# tx-qo100-v3.net
KiCad netlist of a schematic drawn in EAGLE
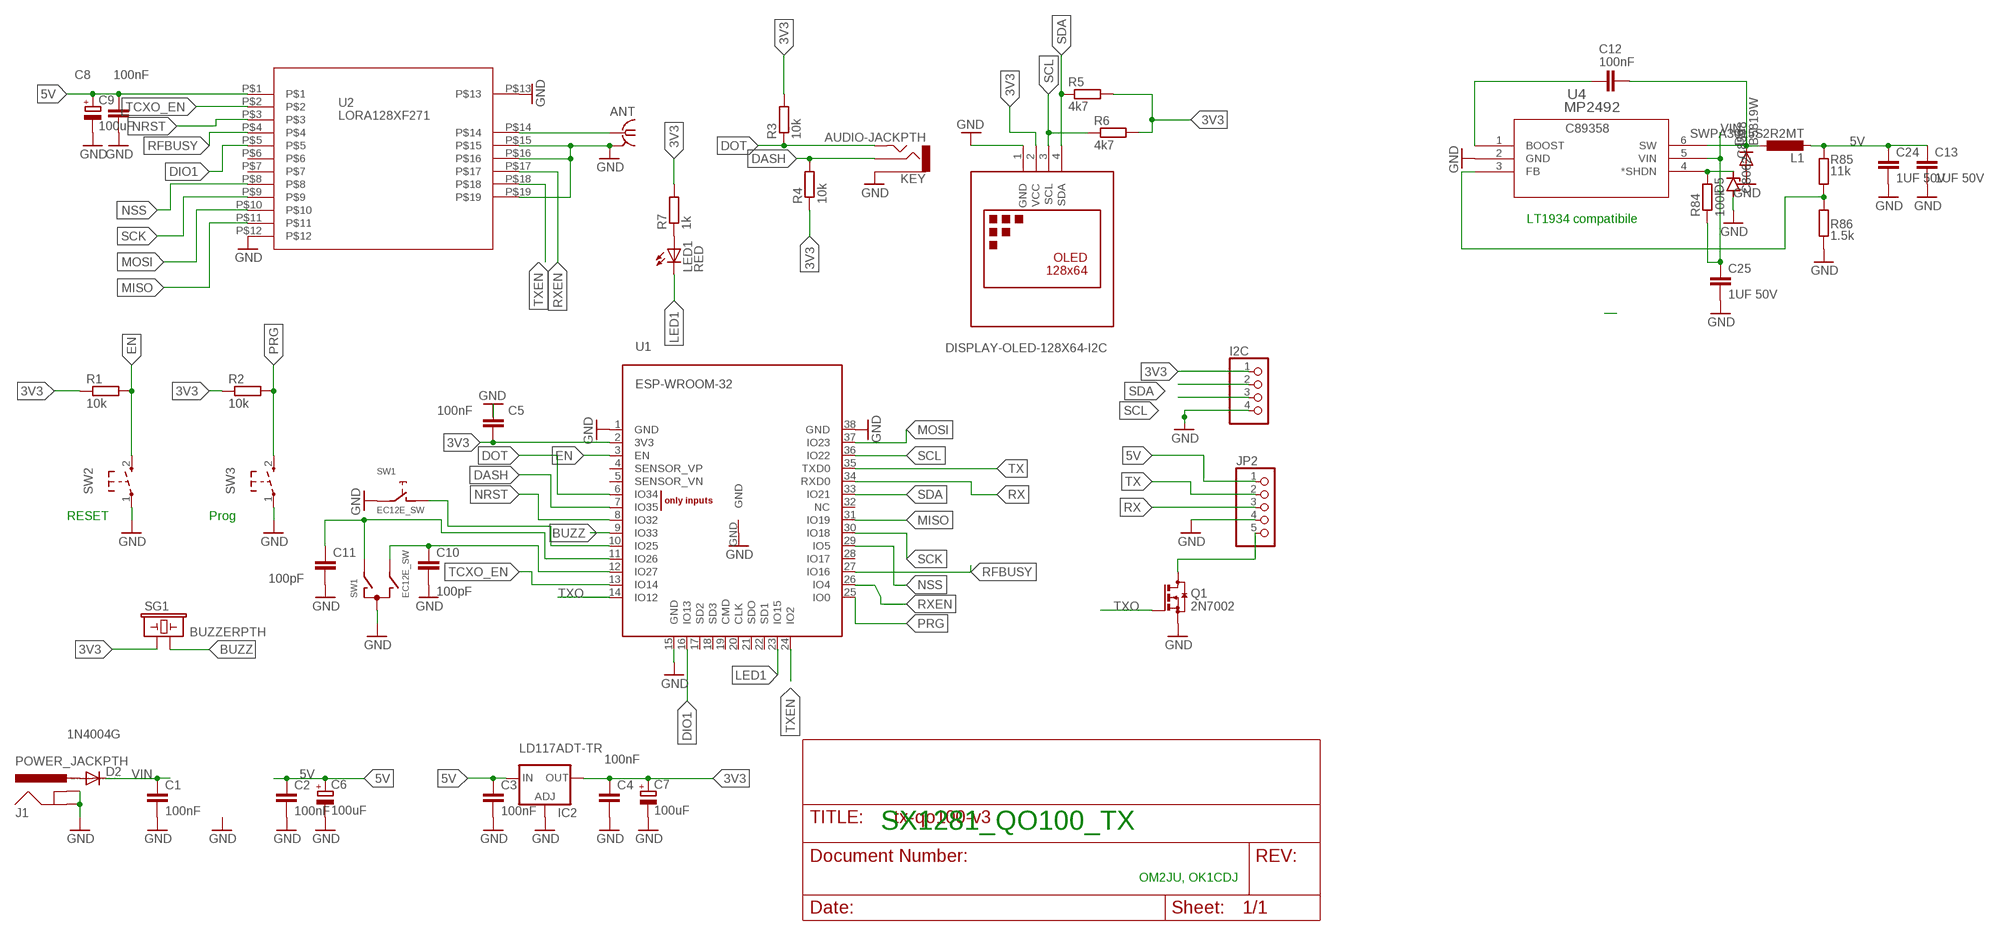
[diagram p0: schematic, sheet 1]

(export (version "E")
  (design (tool "Eeschema 10.0.6"))
  (components
    (comp (ref "ANT")
      (value "SMA-142-0711-821/826")
      (footprint "eagle-import:J502-ND-142-0711-821_826")
      (fields (field (name "MF") "JOHNSON COMPONENTS") (field (name "MPN") "142-0711-821"))
      (libsource (lib "eagle-import") (part "SMA-142-0711-821/826"))
    )
    (comp (ref "C1")
      (value "100nF")
      (footprint "eagle-import:C0603")
      (libsource (lib "eagle-import") (part "C-EUC0603"))
    )
    (comp (ref "C2")
      (value "100nF")
      (footprint "eagle-import:C0603")
      (libsource (lib "eagle-import") (part "C-EUC0603"))
    )
    (comp (ref "C3")
      (value "100nF")
      (footprint "eagle-import:C0603")
      (libsource (lib "eagle-import") (part "C-EUC0603"))
    )
    (comp (ref "C4")
      (value "100nF")
      (footprint "eagle-import:C0603")
      (libsource (lib "eagle-import") (part "C-EUC0603"))
    )
    (comp (ref "C5")
      (value "100nF")
      (footprint "eagle-import:C0603")
      (libsource (lib "eagle-import") (part "C-EUC0603"))
    )
    (comp (ref "C6")
      (value "100uF")
      (footprint "eagle-import:SMC_B")
      (fields (field (name "LCSC_PART") "C16133"))
      (libsource (lib "eagle-import") (part "CPOL-EUSMCB"))
    )
    (comp (ref "C7")
      (value "100uF")
      (footprint "eagle-import:SMC_B")
      (fields (field (name "LCSC_PART") "C16133"))
      (libsource (lib "eagle-import") (part "CPOL-EUSMCB"))
    )
    (comp (ref "C8")
      (value "100nF")
      (footprint "eagle-import:C0603")
      (libsource (lib "eagle-import") (part "C-EUC0603"))
    )
    (comp (ref "C9")
      (value "100uF")
      (footprint "eagle-import:SMC_B")
      (fields (field (name "LCSC_PART") "C16133"))
      (libsource (lib "eagle-import") (part "CPOL-EUSMCB"))
    )
    (comp (ref "C10")
      (value "100pF")
      (footprint "eagle-import:C0603")
      (libsource (lib "eagle-import") (part "C-EUC0603"))
    )
    (comp (ref "C11")
      (value "100pF")
      (footprint "eagle-import:C0603")
      (libsource (lib "eagle-import") (part "C-EUC0603"))
    )
    (comp (ref "C12")
      (value "100nF")
      (footprint "eagle-import:C0603")
      (libsource (lib "eagle-import") (part "C-EUC0603"))
    )
    (comp (ref "C13")
      (value "1UF 50V")
      (footprint "eagle-import:C0603")
      (fields (field (name "LCSC_PART") "C15849"))
      (libsource (lib "eagle-import") (part "C-EUC0603"))
    )
    (comp (ref "C24")
      (value "1UF 50V")
      (footprint "eagle-import:C0603")
      (fields (field (name "LCSC_PART") "C15849"))
      (libsource (lib "eagle-import") (part "C-EUC0603"))
    )
    (comp (ref "C25")
      (value "1UF 50V")
      (footprint "eagle-import:C0603")
      (fields (field (name "LCSC_PART") "C15849"))
      (libsource (lib "eagle-import") (part "C-EUC0603"))
    )
    (comp (ref "D2")
      (value "1N4004G")
      (footprint "eagle-import:DO-214AC")
      (fields (field (name "LCSC_PART") "C433394"))
      (libsource (lib "eagle-import") (part "DIODE-DO-214AC"))
    )
    (comp (ref "D5")
      (value "C8062")
      (footprint "eagle-import:SOD80C")
      (libsource (lib "eagle-import") (part "ZENER-DIODESOD80C"))
    )
    (comp (ref "D6")
      (value "B5819W")
      (footprint "eagle-import:SOD123")
      (fields (field (name "LCSC_PART") "C8598"))
      (libsource (lib "eagle-import") (part "DIODE-SOD123"))
    )
    (comp (ref "I2C")
      (value "PINHD-1X4")
      (footprint "eagle-import:1X04")
      (libsource (lib "eagle-import") (part "PINHD-1X4"))
    )
    (comp (ref "IC2")
      (value "LD117ADT-TR")
      (footprint "eagle-import:DPACK")
      (fields (field (name "LCSC_PART") "C358375"))
      (libsource (lib "eagle-import") (part "LD117A?DT-TR"))
    )
    (comp (ref "J1")
      (value "POWER_JACKPTH")
      (footprint "eagle-import:POWER_JACK_PTH")
      (libsource (lib "eagle-import") (part "POWER_JACKPTH"))
    )
    (comp (ref "JP2")
      (value "PINHD-1X5/90")
      (footprint "eagle-import:1X05_90")
      (libsource (lib "eagle-import") (part "PINHD-1X5/90"))
    )
    (comp (ref "KEY")
      (value "AUDIO-JACKPTH")
      (footprint "eagle-import:AUDIO-JACK")
      (libsource (lib "eagle-import") (part "AUDIO-JACKPTH"))
    )
    (comp (ref "L1")
      (value "SWPA3015S2R2MT")
      (footprint "eagle-import:L2825P")
      (fields (field (name "LCSC_PART") "C43389"))
      (libsource (lib "eagle-import") (part "L-EUL2825P"))
    )
    (comp (ref "LED1")
      (value "RED")
      (footprint "eagle-import:CHIP-LED0805")
      (fields (field (name "LCSC_PART") "C84256"))
      (libsource (lib "eagle-import") (part "LEDCHIP-LED0805"))
    )
    (comp (ref "Q1")
      (value "2N7002")
      (footprint "eagle-import:SOT23")
      (fields (field (name "LCSC_PART") "C8545"))
      (libsource (lib "eagle-import") (part "BSS123"))
    )
    (comp (ref "R1")
      (value "10k")
      (footprint "eagle-import:R0603")
      (libsource (lib "eagle-import") (part "R-EU_R0603"))
    )
    (comp (ref "R2")
      (value "10k")
      (footprint "eagle-import:R0603")
      (libsource (lib "eagle-import") (part "R-EU_R0603"))
    )
    (comp (ref "R3")
      (value "10k")
      (footprint "eagle-import:R0603")
      (libsource (lib "eagle-import") (part "R-EU_R0603"))
    )
    (comp (ref "R4")
      (value "10k")
      (footprint "eagle-import:R0603")
      (libsource (lib "eagle-import") (part "R-EU_R0603"))
    )
    (comp (ref "R5")
      (value "4k7")
      (footprint "eagle-import:R0603")
      (libsource (lib "eagle-import") (part "R-EU_R0603"))
    )
    (comp (ref "R6")
      (value "4k7")
      (footprint "eagle-import:R0603")
      (libsource (lib "eagle-import") (part "R-EU_R0603"))
    )
    (comp (ref "R7")
      (value "1k")
      (footprint "eagle-import:R0603")
      (libsource (lib "eagle-import") (part "R-EU_R0603"))
    )
    (comp (ref "R84")
      (value "100k")
      (footprint "eagle-import:R0603")
      (libsource (lib "eagle-import") (part "R-EU_R0603"))
    )
    (comp (ref "R85")
      (value "11k")
      (footprint "eagle-import:R0603")
      (libsource (lib "eagle-import") (part "R-EU_R0603"))
    )
    (comp (ref "R86")
      (value "1.5k")
      (footprint "eagle-import:R0603")
      (libsource (lib "eagle-import") (part "R-EU_R0603"))
    )
    (comp (ref "SG1")
      (value "BUZZERPTH")
      (footprint "eagle-import:BUZZER-12MM")
      (fields (field (name "LCSC_PART") "C360607"))
      (libsource (lib "eagle-import") (part "BUZZERPTH"))
    )
    (comp (ref "SW1")
      (value "EC12E_SW")
      (footprint "eagle-import:ALPS_EC12E_SW")
      (fields (field (name "MPN") "EC12E2424407"))
      (libsource (lib "eagle-import") (part "EC12E_SW"))
    )
    (comp (ref "SW2")
      (value "SW_TACT_2P-3X6")
      (footprint "eagle-import:SW_TACT_3X6")
      (fields (field (name "LCSC_PART") "C520860"))
      (libsource (lib "eagle-import") (part "SW_TACT_2P-3X6"))
    )
    (comp (ref "SW3")
      (value "SW_TACT_2P-3X6")
      (footprint "eagle-import:SW_TACT_3X6")
      (fields (field (name "LCSC_PART") "C520860"))
      (libsource (lib "eagle-import") (part "SW_TACT_2P-3X6"))
    )
    (comp (ref "U$1")
      (value "DISPLAY-OLED-128X64-I2C")
      (footprint "eagle-import:DISPLAY-OLED-128X64-I2C")
      (libsource (lib "eagle-import") (part "DISPLAY-OLED-128X64-I2C"))
    )
    (comp (ref "U1")
      (value "ESP-WROOM-32")
      (footprint "eagle-import:ESP-WROOM-32")
      (libsource (lib "eagle-import") (part "ESP-WROOM-32"))
    )
    (comp (ref "U2")
      (value "LORA128XF271")
      (footprint "eagle-import:LORA128XF27")
      (libsource (lib "eagle-import") (part "LORA128XF271"))
    )
    (comp (ref "U4")
      (value "MP2492")
      (footprint "eagle-import:SOT-6_S")
      (fields
        (field (name "DIGI-KEY_PART_NUMBER") "LT1934ES6#TRMPBFCT-ND")
        (field (name "MF") "Linear Technology/Analog")
        (field (name "MP") "LT1934ES6#TRMPBF")
        (field (name "LCSC_PART") "C89358")
      )
      (libsource (lib "eagle-import") (part "LT1934ES6TRMPBF"))
    )
  )
  (nets
    (net (code "1") (name "/TXO") (class "Default")
      (node (ref "Q1") (pin "1") (pinfunction "G_1") (pintype "passive"))
      (node (ref "U1") (pin "14") (pinfunction "IO12_14") (pintype "bidirectional"))
    )
    (net (code "2") (name "/VIN") (class "Default")
      (node (ref "C1") (pin "1") (pinfunction "1_1") (pintype "passive"))
      (node (ref "C25") (pin "1") (pinfunction "1_1") (pintype "passive"))
      (node (ref "D2") (pin "C") (pinfunction "C_C") (pintype "passive"))
      (node (ref "R84") (pin "1") (pinfunction "1_1") (pintype "passive"))
      (node (ref "U4") (pin "5") (pinfunction "VIN_5") (pintype "power_in"))
    )
    (net (code "3") (name "3V3") (class "Default")
      (node (ref "C4") (pin "1") (pinfunction "1_1") (pintype "passive"))
      (node (ref "C5") (pin "1") (pinfunction "1_1") (pintype "passive"))
      (node (ref "C7") (pin "+") (pinfunction "+_+") (pintype "passive"))
      (node (ref "I2C") (pin "1") (pinfunction "1_1") (pintype "passive"))
      (node (ref "IC2") (pin "4") (pinfunction "OUT_4") (pintype "passive"))
      (node (ref "R1") (pin "1") (pinfunction "1_1") (pintype "passive"))
      (node (ref "R2") (pin "1") (pinfunction "1_1") (pintype "passive"))
      (node (ref "R3") (pin "2") (pinfunction "2_2") (pintype "passive"))
      (node (ref "R4") (pin "1") (pinfunction "1_1") (pintype "passive"))
      (node (ref "R5") (pin "2") (pinfunction "2_2") (pintype "passive"))
      (node (ref "R6") (pin "2") (pinfunction "2_2") (pintype "passive"))
      (node (ref "R7") (pin "2") (pinfunction "2_2") (pintype "passive"))
      (node (ref "SG1") (pin "+") (pinfunction "1_+") (pintype "passive"))
      (node (ref "U$1") (pin "2") (pinfunction "VCC_2") (pintype "power_in"))
      (node (ref "U1") (pin "2") (pinfunction "3V3_2") (pintype "bidirectional"))
    )
    (net (code "4") (name "5V") (class "Default")
      (node (ref "C13") (pin "1") (pinfunction "1_1") (pintype "passive"))
      (node (ref "C2") (pin "1") (pinfunction "1_1") (pintype "passive"))
      (node (ref "C24") (pin "1") (pinfunction "1_1") (pintype "passive"))
      (node (ref "C3") (pin "1") (pinfunction "1_1") (pintype "passive"))
      (node (ref "C6") (pin "+") (pinfunction "+_+") (pintype "passive"))
      (node (ref "C8") (pin "1") (pinfunction "1_1") (pintype "passive"))
      (node (ref "C9") (pin "+") (pinfunction "+_+") (pintype "passive"))
      (node (ref "IC2") (pin "3") (pinfunction "IN_3") (pintype "input"))
      (node (ref "JP2") (pin "1") (pinfunction "1_1") (pintype "passive"))
      (node (ref "L1") (pin "2") (pinfunction "2_2") (pintype "passive"))
      (node (ref "R85") (pin "1") (pinfunction "1_1") (pintype "passive"))
      (node (ref "U2") (pin "P$1") (pinfunction "P$1_P$1") (pintype "bidirectional"))
    )
    (net (code "5") (name "BUZZ") (class "Default")
      (node (ref "SG1") (pin "-") (pinfunction "2_-") (pintype "passive"))
      (node (ref "U1") (pin "9") (pinfunction "IO33_9") (pintype "bidirectional"))
    )
    (net (code "6") (name "DASH") (class "Default")
      (node (ref "KEY") (pin "2") (pinfunction "2_2") (pintype "bidirectional"))
      (node (ref "R4") (pin "2") (pinfunction "2_2") (pintype "passive"))
      (node (ref "U1") (pin "7") (pinfunction "IO35_7") (pintype "input"))
    )
    (net (code "7") (name "DIO1") (class "Default")
      (node (ref "U1") (pin "16") (pinfunction "IO13_16") (pintype "bidirectional"))
      (node (ref "U2") (pin "P$5") (pinfunction "P$5_P$5") (pintype "bidirectional"))
    )
    (net (code "8") (name "DOT") (class "Default")
      (node (ref "KEY") (pin "5") (pinfunction "5_5") (pintype "bidirectional"))
      (node (ref "R3") (pin "1") (pinfunction "1_1") (pintype "passive"))
      (node (ref "U1") (pin "6") (pinfunction "IO34_6") (pintype "input"))
    )
    (net (code "9") (name "EN") (class "Default")
      (node (ref "R1") (pin "2") (pinfunction "2_2") (pintype "passive"))
      (node (ref "SW2") (pin "2") (pinfunction "3_2") (pintype "passive"))
      (node (ref "U1") (pin "3") (pinfunction "EN_3") (pintype "bidirectional"))
    )
    (net (code "10") (name "GND") (class "Default")
      (node (ref "ANT") (pin "G@1") (pinfunction "2_G@1") (pintype "passive"))
      (node (ref "ANT") (pin "G@2") (pinfunction "2_G@2") (pintype "passive"))
      (node (ref "ANT") (pin "G@3") (pinfunction "2_G@3") (pintype "passive"))
      (node (ref "ANT") (pin "G@4") (pinfunction "2_G@4") (pintype "passive"))
      (node (ref "C1") (pin "2") (pinfunction "2_2") (pintype "passive"))
      (node (ref "C10") (pin "2") (pinfunction "2_2") (pintype "passive"))
      (node (ref "C11") (pin "2") (pinfunction "2_2") (pintype "passive"))
      (node (ref "C13") (pin "2") (pinfunction "2_2") (pintype "passive"))
      (node (ref "C2") (pin "2") (pinfunction "2_2") (pintype "passive"))
      (node (ref "C24") (pin "2") (pinfunction "2_2") (pintype "passive"))
      (node (ref "C25") (pin "2") (pinfunction "2_2") (pintype "passive"))
      (node (ref "C3") (pin "2") (pinfunction "2_2") (pintype "passive"))
      (node (ref "C4") (pin "2") (pinfunction "2_2") (pintype "passive"))
      (node (ref "C5") (pin "2") (pinfunction "2_2") (pintype "passive"))
      (node (ref "C6") (pin "-") (pinfunction "-_-") (pintype "passive"))
      (node (ref "C7") (pin "-") (pinfunction "-_-") (pintype "passive"))
      (node (ref "C8") (pin "2") (pinfunction "2_2") (pintype "passive"))
      (node (ref "C9") (pin "-") (pinfunction "-_-") (pintype "passive"))
      (node (ref "D5") (pin "A") (pinfunction "A_A") (pintype "passive"))
      (node (ref "D6") (pin "A") (pinfunction "A_A") (pintype "passive"))
      (node (ref "I2C") (pin "4") (pinfunction "4_4") (pintype "passive"))
      (node (ref "IC2") (pin "1") (pinfunction "ADJ_1") (pintype "input"))
      (node (ref "J1") (pin "GND") (pinfunction "GND_GND") (pintype "bidirectional"))
      (node (ref "J1") (pin "GNDBREAK") (pinfunction "GNDBREAK_GNDBREAK") (pintype "bidirectional"))
      (node (ref "JP2") (pin "4") (pinfunction "4_4") (pintype "passive"))
      (node (ref "KEY") (pin "1") (pinfunction "1_1") (pintype "bidirectional"))
      (node (ref "Q1") (pin "2") (pinfunction "S_2") (pintype "passive"))
      (node (ref "R86") (pin "1") (pinfunction "1_1") (pintype "passive"))
      (node (ref "SW1") (pin "C") (pinfunction "C_C") (pintype "passive"))
      (node (ref "SW1") (pin "E") (pinfunction "2_E") (pintype "passive"))
      (node (ref "SW2") (pin "1") (pinfunction "1_1") (pintype "passive"))
      (node (ref "SW3") (pin "1") (pinfunction "1_1") (pintype "passive"))
      (node (ref "U$1") (pin "1") (pinfunction "GND_1") (pintype "power_in"))
      (node (ref "U1") (pin "1") (pinfunction "GND_1") (pintype "bidirectional"))
      (node (ref "U1") (pin "15") (pinfunction "GND_15") (pintype "bidirectional"))
      (node (ref "U1") (pin "38") (pinfunction "GND_38") (pintype "bidirectional"))
      (node (ref "U1") (pin "GND") (pinfunction "GND_GND") (pintype "bidirectional"))
      (node (ref "U2") (pin "P$12") (pinfunction "P$12_P$12") (pintype "bidirectional"))
      (node (ref "U2") (pin "P$13") (pinfunction "P$13_P$13") (pintype "bidirectional"))
      (node (ref "U2") (pin "P$15") (pinfunction "P$15_P$15") (pintype "bidirectional"))
      (node (ref "U2") (pin "P$16") (pinfunction "P$16_P$16") (pintype "bidirectional"))
      (node (ref "U2") (pin "P$19") (pinfunction "P$19_P$19") (pintype "bidirectional"))
      (node (ref "U4") (pin "2") (pinfunction "GND_2") (pintype "power_in"))
    )
    (net (code "11") (name "LED1") (class "Default")
      (node (ref "LED1") (pin "C") (pinfunction "C_C") (pintype "passive"))
      (node (ref "U1") (pin "23") (pinfunction "IO15_23") (pintype "bidirectional"))
    )
    (net (code "12") (name "MISO") (class "Default")
      (node (ref "U1") (pin "31") (pinfunction "IO19_31") (pintype "bidirectional"))
      (node (ref "U2") (pin "P$11") (pinfunction "P$11_P$11") (pintype "bidirectional"))
    )
    (net (code "13") (name "MOSI") (class "Default")
      (node (ref "U1") (pin "37") (pinfunction "IO23_37") (pintype "bidirectional"))
      (node (ref "U2") (pin "P$10") (pinfunction "P$10_P$10") (pintype "bidirectional"))
    )
    (net (code "14") (name "NRST") (class "Default")
      (node (ref "U1") (pin "8") (pinfunction "IO32_8") (pintype "bidirectional"))
      (node (ref "U2") (pin "P$3") (pinfunction "P$3_P$3") (pintype "bidirectional"))
    )
    (net (code "15") (name "NSS") (class "Default")
      (node (ref "U1") (pin "29") (pinfunction "IO5_29") (pintype "bidirectional"))
      (node (ref "U2") (pin "P$8") (pinfunction "P$8_P$8") (pintype "bidirectional"))
    )
    (net (code "16") (name "Net-(ANT-Pad1)") (class "Default")
      (node (ref "ANT") (pin "1") (pinfunction "1_1") (pintype "passive"))
      (node (ref "U2") (pin "P$14") (pinfunction "P$14_P$14") (pintype "bidirectional"))
    )
    (net (code "17") (name "Net-(D2-PadA)") (class "Default")
      (node (ref "D2") (pin "A") (pinfunction "A_A") (pintype "passive"))
      (node (ref "J1") (pin "PWR") (pinfunction "PWR_PWR") (pintype "bidirectional"))
    )
    (net (code "18") (name "Net-(LED1-PadA)") (class "Default")
      (node (ref "LED1") (pin "A") (pinfunction "A_A") (pintype "passive"))
      (node (ref "R7") (pin "1") (pinfunction "1_1") (pintype "passive"))
    )
    (net (code "19") (name "Net-(Q1-D)") (class "Default")
      (node (ref "JP2") (pin "5") (pinfunction "5_5") (pintype "passive"))
      (node (ref "Q1") (pin "3") (pinfunction "D_3") (pintype "passive"))
    )
    (net (code "20") (name "Net-(SW1B-1)") (class "Default")
      (node (ref "SW1") (pin "D") (pinfunction "1_D") (pintype "passive"))
      (node (ref "U1") (pin "10") (pinfunction "IO25_10") (pintype "bidirectional"))
    )
    (net (code "21") (name "Net-(U1-IO26)") (class "Default")
      (node (ref "C11") (pin "1") (pinfunction "1_1") (pintype "passive"))
      (node (ref "SW1") (pin "A") (pinfunction "A_A") (pintype "passive"))
      (node (ref "U1") (pin "11") (pinfunction "IO26_11") (pintype "bidirectional"))
    )
    (net (code "22") (name "Net-(U1-IO27)") (class "Default")
      (node (ref "C10") (pin "1") (pinfunction "1_1") (pintype "passive"))
      (node (ref "SW1") (pin "B") (pinfunction "B_B") (pintype "passive"))
      (node (ref "U1") (pin "12") (pinfunction "IO27_12") (pintype "bidirectional"))
    )
    (net (code "23") (name "Net-(U4-*SHDN)") (class "Default")
      (node (ref "D5") (pin "C") (pinfunction "C_C") (pintype "passive"))
      (node (ref "R84") (pin "2") (pinfunction "2_2") (pintype "passive"))
      (node (ref "U4") (pin "4") (pinfunction "*SHDN_4") (pintype "passive"))
    )
    (net (code "24") (name "Net-(U4-BOOST)") (class "Default")
      (node (ref "C12") (pin "2") (pinfunction "2_2") (pintype "passive"))
      (node (ref "U4") (pin "1") (pinfunction "BOOST_1") (pintype "passive"))
    )
    (net (code "25") (name "Net-(U4-FB)") (class "Default")
      (node (ref "R85") (pin "2") (pinfunction "2_2") (pintype "passive"))
      (node (ref "R86") (pin "2") (pinfunction "2_2") (pintype "passive"))
      (node (ref "U4") (pin "3") (pinfunction "FB_3") (pintype "passive"))
    )
    (net (code "26") (name "Net-(U4-SW)") (class "Default")
      (node (ref "C12") (pin "1") (pinfunction "1_1") (pintype "passive"))
      (node (ref "D6") (pin "C") (pinfunction "C_C") (pintype "passive"))
      (node (ref "L1") (pin "1") (pinfunction "1_1") (pintype "passive"))
      (node (ref "U4") (pin "6") (pinfunction "SW_6") (pintype "passive"))
    )
    (net (code "27") (name "PRG") (class "Default")
      (node (ref "R2") (pin "2") (pinfunction "2_2") (pintype "passive"))
      (node (ref "SW3") (pin "2") (pinfunction "3_2") (pintype "passive"))
      (node (ref "U1") (pin "25") (pinfunction "IO0_25") (pintype "bidirectional"))
    )
    (net (code "28") (name "RFBUSY") (class "Default")
      (node (ref "U1") (pin "27") (pinfunction "IO16_27") (pintype "bidirectional"))
      (node (ref "U2") (pin "P$4") (pinfunction "P$4_P$4") (pintype "bidirectional"))
    )
    (net (code "29") (name "RX") (class "Default")
      (node (ref "JP2") (pin "3") (pinfunction "3_3") (pintype "passive"))
      (node (ref "U1") (pin "34") (pinfunction "RXD0_34") (pintype "bidirectional"))
    )
    (net (code "30") (name "RXEN") (class "Default")
      (node (ref "U1") (pin "26") (pinfunction "IO4_26") (pintype "bidirectional"))
      (node (ref "U2") (pin "P$17") (pinfunction "P$17_P$17") (pintype "bidirectional"))
    )
    (net (code "31") (name "SCK") (class "Default")
      (node (ref "U1") (pin "30") (pinfunction "IO18_30") (pintype "bidirectional"))
      (node (ref "U2") (pin "P$9") (pinfunction "P$9_P$9") (pintype "bidirectional"))
    )
    (net (code "32") (name "SCL") (class "Default")
      (node (ref "I2C") (pin "3") (pinfunction "3_3") (pintype "passive"))
      (node (ref "R6") (pin "1") (pinfunction "1_1") (pintype "passive"))
      (node (ref "U$1") (pin "3") (pinfunction "SCL_3") (pintype "bidirectional"))
      (node (ref "U1") (pin "36") (pinfunction "IO22_36") (pintype "bidirectional"))
    )
    (net (code "33") (name "SDA") (class "Default")
      (node (ref "I2C") (pin "2") (pinfunction "2_2") (pintype "passive"))
      (node (ref "R5") (pin "1") (pinfunction "1_1") (pintype "passive"))
      (node (ref "U$1") (pin "4") (pinfunction "SDA_4") (pintype "bidirectional"))
      (node (ref "U1") (pin "33") (pinfunction "IO21_33") (pintype "bidirectional"))
    )
    (net (code "34") (name "TCXO_EN") (class "Default")
      (node (ref "U1") (pin "13") (pinfunction "IO14_13") (pintype "bidirectional"))
      (node (ref "U2") (pin "P$2") (pinfunction "P$2_P$2") (pintype "bidirectional"))
    )
    (net (code "35") (name "TX") (class "Default")
      (node (ref "JP2") (pin "2") (pinfunction "2_2") (pintype "passive"))
      (node (ref "U1") (pin "35") (pinfunction "TXD0_35") (pintype "bidirectional"))
    )
    (net (code "36") (name "TXEN") (class "Default")
      (node (ref "U1") (pin "24") (pinfunction "IO2_24") (pintype "bidirectional"))
      (node (ref "U2") (pin "P$18") (pinfunction "P$18_P$18") (pintype "bidirectional"))
    )
    (net (code "37") (name "unconnected-(U1-CLK-Pad20)") (class "Default")
      (node (ref "U1") (pin "20") (pinfunction "CLK_20") (pintype "bidirectional"))
    )
    (net (code "38") (name "unconnected-(U1-CMD-Pad19)") (class "Default")
      (node (ref "U1") (pin "19") (pinfunction "CMD_19") (pintype "bidirectional"))
    )
    (net (code "39") (name "unconnected-(U1-IO17-Pad28)") (class "Default")
      (node (ref "U1") (pin "28") (pinfunction "IO17_28") (pintype "bidirectional"))
    )
    (net (code "40") (name "unconnected-(U1-NC-Pad32)") (class "Default")
      (node (ref "U1") (pin "32") (pinfunction "NC_32") (pintype "bidirectional"))
    )
    (net (code "41") (name "unconnected-(U1-SD1-Pad22)") (class "Default")
      (node (ref "U1") (pin "22") (pinfunction "SD1_22") (pintype "bidirectional"))
    )
    (net (code "42") (name "unconnected-(U1-SD2-Pad17)") (class "Default")
      (node (ref "U1") (pin "17") (pinfunction "SD2_17") (pintype "bidirectional"))
    )
    (net (code "43") (name "unconnected-(U1-SD3-Pad18)") (class "Default")
      (node (ref "U1") (pin "18") (pinfunction "SD3_18") (pintype "bidirectional"))
    )
    (net (code "44") (name "unconnected-(U1-SDO-Pad21)") (class "Default")
      (node (ref "U1") (pin "21") (pinfunction "SDO_21") (pintype "bidirectional"))
    )
    (net (code "45") (name "unconnected-(U1-SENSOR_VN-Pad5)") (class "Default")
      (node (ref "U1") (pin "5") (pinfunction "SENSOR_VN_5") (pintype "input"))
    )
    (net (code "46") (name "unconnected-(U1-SENSOR_VP-Pad4)") (class "Default")
      (node (ref "U1") (pin "4") (pinfunction "SENSOR_VP_4") (pintype "input"))
    )
    (net (code "47") (name "unconnected-(U2-PadP$6)") (class "Default")
      (node (ref "U2") (pin "P$6") (pinfunction "P$6_P$6") (pintype "bidirectional"))
    )
    (net (code "48") (name "unconnected-(U2-PadP$7)") (class "Default")
      (node (ref "U2") (pin "P$7") (pinfunction "P$7_P$7") (pintype "bidirectional"))
    )
  )
)
